# Spolerigg3.net
KiCad netlist of a schematic drawn in Altium Designer
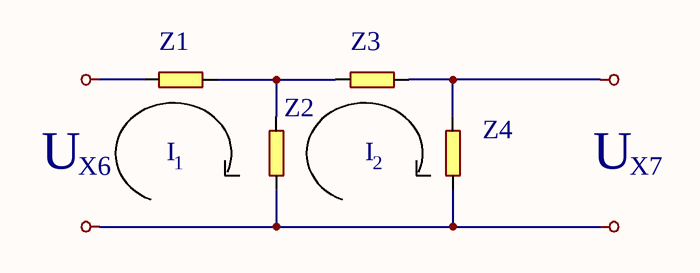
[diagram p0: Spolerigg3.SchDoc]

(export (version "E")
  (design (tool "Eeschema 10.0.6"))
  (components
    (comp (ref "Z1")
      (value "1.0")
      (footprint "RESA_0.25W")
      (description "0.25W 1% Generic resistor")
      (libsource (lib "OVLib") (part "Resistor2"))
    )
    (comp (ref "Z2")
      (value "1.0")
      (footprint "RESA_0.25W")
      (description "0.25W 1% Generic resistor")
      (libsource (lib "") (part "Resistor2_1"))
    )
    (comp (ref "Z3")
      (value "1.0")
      (footprint "RESA_0.25W")
      (description "0.25W 1% Generic resistor")
      (libsource (lib "OVLib") (part "Resistor2"))
    )
    (comp (ref "Z4")
      (value "1.0")
      (footprint "RESA_0.25W")
      (description "0.25W 1% Generic resistor")
      (libsource (lib "") (part "Resistor2_1"))
    )
  )
  (nets
    (net (code "1") (name "GND") (class "Default")
      (node (ref "Z2") (pin "1") (pinfunction "1_1") (pintype "passive"))
      (node (ref "Z4") (pin "1") (pinfunction "1_1") (pintype "passive"))
    )
    (net (code "2") (name "IN") (class "Default")
      (node (ref "Z1") (pin "1") (pinfunction "1_1") (pintype "passive"))
    )
    (net (code "3") (name "Net-(Z1-Pad2)") (class "Default")
      (node (ref "Z1") (pin "2") (pinfunction "2_2") (pintype "passive"))
      (node (ref "Z2") (pin "2") (pinfunction "2_2") (pintype "passive"))
      (node (ref "Z3") (pin "1") (pinfunction "1_1") (pintype "passive"))
    )
    (net (code "4") (name "OUT") (class "Default")
      (node (ref "Z3") (pin "2") (pinfunction "2_2") (pintype "passive"))
      (node (ref "Z4") (pin "2") (pinfunction "2_2") (pintype "passive"))
    )
  )
)
